# PCB-SSB-1x2b.net
KiCad netlist of a schematic drawn in EAGLE
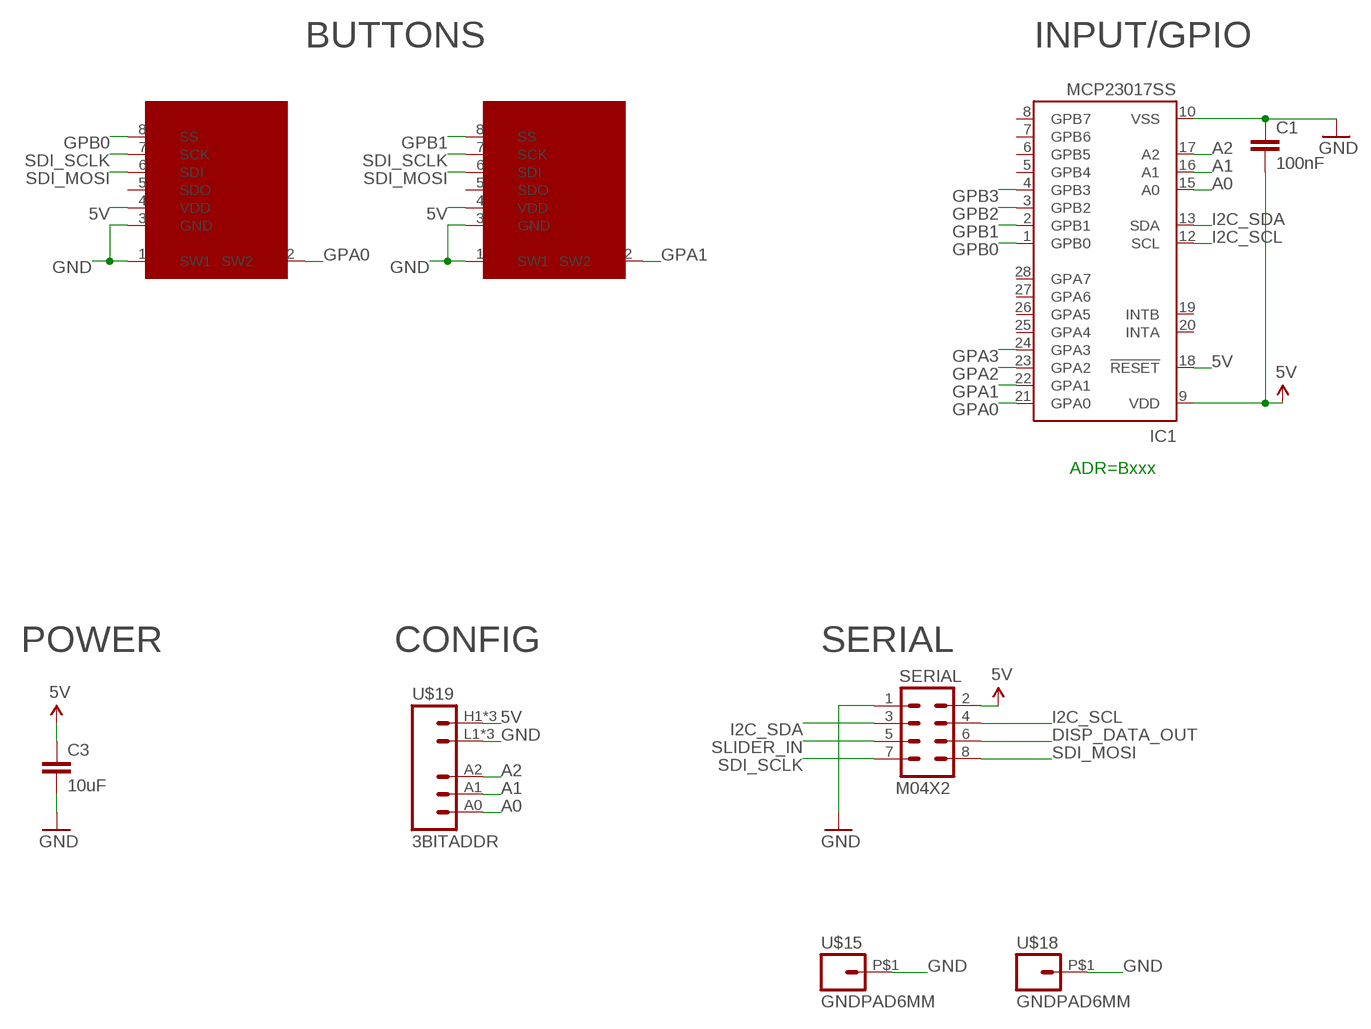
[diagram p0: schematic, sheet 1]

(export (version "E")
  (design (tool "Eeschema 10.0.6"))
  (components
    (comp (ref "C1")
      (value "100nF")
      (footprint "eagle-import:0603-CAP")
      (libsource (lib "eagle-import") (part "CAP0603-CAP"))
    )
    (comp (ref "C3")
      (value "10uF")
      (footprint "eagle-import:0805")
      (libsource (lib "eagle-import") (part "CAP0805"))
    )
    (comp (ref "IC1")
      (value "MCP23017SS")
      (footprint "eagle-import:SSOP28")
      (fields
        (field (name "MF") "MICROCHIP")
        (field (name "MPN") "MCP23017-E/SS")
        (field (name "MPN_1") "MCP23017-E/SS")
        (field (name "OC_FARNELL") "1467674")
        (field (name "OC_NEWARK") "31K2960")
      )
      (libsource (lib "eagle-import") (part "MCP23017SS"))
    )
    (comp (ref "SERIAL")
      (value "M04X2")
      (footprint "eagle-import:2X4")
      (libsource (lib "eagle-import") (part "M04X2"))
    )
    (comp (ref "SSW1")
      (value "SMART_SWITCHSMART_SWITCH_8PIN")
      (footprint "eagle-import:SMART_SWITCH")
      (libsource (lib "eagle-import") (part "SMART_SWITCHSMART_SWITCH_8PIN"))
    )
    (comp (ref "SSW2")
      (value "SMART_SWITCHSMART_SWITCH_8PIN")
      (footprint "eagle-import:SMART_SWITCH")
      (libsource (lib "eagle-import") (part "SMART_SWITCHSMART_SWITCH_8PIN"))
    )
    (comp (ref "U$15")
      (value "GNDPAD6MM")
      (footprint "eagle-import:3.2MMPAD6MM")
      (libsource (lib "eagle-import") (part "GNDPAD6MM"))
    )
    (comp (ref "U$18")
      (value "GNDPAD6MM")
      (footprint "eagle-import:3.2MMPAD6MM")
      (libsource (lib "eagle-import") (part "GNDPAD6MM"))
    )
    (comp (ref "U$19")
      (value "3BITADDR")
      (footprint "eagle-import:3BITADDR")
      (libsource (lib "eagle-import") (part "3BITADDR"))
    )
  )
  (nets
    (net (code "1") (name "/A0") (class "Default")
      (node (ref "IC1") (pin "15") (pinfunction "A0_15") (pintype "input"))
      (node (ref "U$19") (pin "A0") (pinfunction "A0_A0") (pintype "passive"))
    )
    (net (code "2") (name "/A1") (class "Default")
      (node (ref "IC1") (pin "16") (pinfunction "A1_16") (pintype "input"))
      (node (ref "U$19") (pin "A1") (pinfunction "A1_A1") (pintype "passive"))
    )
    (net (code "3") (name "/A2") (class "Default")
      (node (ref "IC1") (pin "17") (pinfunction "A2_17") (pintype "input"))
      (node (ref "U$19") (pin "A2") (pinfunction "A2_A2") (pintype "passive"))
    )
    (net (code "4") (name "/DISP_DATA_OUT") (class "Default")
      (node (ref "SERIAL") (pin "6") (pinfunction "6_6") (pintype "passive"))
    )
    (net (code "5") (name "/GPA0") (class "Default")
      (node (ref "IC1") (pin "21") (pinfunction "GPA0_21") (pintype "bidirectional"))
      (node (ref "SSW1") (pin "2") (pinfunction "SW2_2") (pintype "bidirectional"))
    )
    (net (code "6") (name "/GPA1") (class "Default")
      (node (ref "IC1") (pin "22") (pinfunction "GPA1_22") (pintype "bidirectional"))
      (node (ref "SSW2") (pin "2") (pinfunction "SW2_2") (pintype "bidirectional"))
    )
    (net (code "7") (name "/GPA2") (class "Default")
      (node (ref "IC1") (pin "23") (pinfunction "GPA2_23") (pintype "bidirectional"))
    )
    (net (code "8") (name "/GPA3") (class "Default")
      (node (ref "IC1") (pin "24") (pinfunction "GPA3_24") (pintype "bidirectional"))
    )
    (net (code "9") (name "/GPB0") (class "Default")
      (node (ref "IC1") (pin "1") (pinfunction "GPB0_1") (pintype "bidirectional"))
      (node (ref "SSW1") (pin "8") (pinfunction "SS_8") (pintype "bidirectional"))
    )
    (net (code "10") (name "/GPB1") (class "Default")
      (node (ref "IC1") (pin "2") (pinfunction "GPB1_2") (pintype "bidirectional"))
      (node (ref "SSW2") (pin "8") (pinfunction "SS_8") (pintype "bidirectional"))
    )
    (net (code "11") (name "/GPB2") (class "Default")
      (node (ref "IC1") (pin "3") (pinfunction "GPB2_3") (pintype "bidirectional"))
    )
    (net (code "12") (name "/GPB3") (class "Default")
      (node (ref "IC1") (pin "4") (pinfunction "GPB3_4") (pintype "bidirectional"))
    )
    (net (code "13") (name "/I2C_SCL") (class "Default")
      (node (ref "IC1") (pin "12") (pinfunction "SCL_12") (pintype "input"))
      (node (ref "SERIAL") (pin "4") (pinfunction "4_4") (pintype "passive"))
    )
    (net (code "14") (name "/I2C_SDA") (class "Default")
      (node (ref "IC1") (pin "13") (pinfunction "SDA_13") (pintype "bidirectional"))
      (node (ref "SERIAL") (pin "3") (pinfunction "3_3") (pintype "passive"))
    )
    (net (code "15") (name "/SDI_MOSI") (class "Default")
      (node (ref "SERIAL") (pin "8") (pinfunction "8_8") (pintype "passive"))
      (node (ref "SSW1") (pin "6") (pinfunction "SDI_6") (pintype "bidirectional"))
      (node (ref "SSW2") (pin "6") (pinfunction "SDI_6") (pintype "bidirectional"))
    )
    (net (code "16") (name "/SDI_SCLK") (class "Default")
      (node (ref "SERIAL") (pin "7") (pinfunction "7_7") (pintype "passive"))
      (node (ref "SSW1") (pin "7") (pinfunction "SCK_7") (pintype "bidirectional"))
      (node (ref "SSW2") (pin "7") (pinfunction "SCK_7") (pintype "bidirectional"))
    )
    (net (code "17") (name "/SLIDER_IN") (class "Default")
      (node (ref "SERIAL") (pin "5") (pinfunction "5_5") (pintype "passive"))
    )
    (net (code "18") (name "5V") (class "Default")
      (node (ref "C1") (pin "2") (pinfunction "2_2") (pintype "passive"))
      (node (ref "C3") (pin "1") (pinfunction "1_1") (pintype "passive"))
      (node (ref "IC1") (pin "18") (pinfunction "~{RESET}_18") (pintype "input"))
      (node (ref "IC1") (pin "9") (pinfunction "VDD_9") (pintype "power_in"))
      (node (ref "SERIAL") (pin "2") (pinfunction "2_2") (pintype "passive"))
      (node (ref "SSW1") (pin "4") (pinfunction "VDD_4") (pintype "bidirectional"))
      (node (ref "SSW2") (pin "4") (pinfunction "VDD_4") (pintype "bidirectional"))
      (node (ref "U$19") (pin "H1") (pinfunction "VCC_H1") (pintype "passive"))
      (node (ref "U$19") (pin "H2") (pinfunction "VCC_H2") (pintype "passive"))
      (node (ref "U$19") (pin "H3") (pinfunction "VCC_H3") (pintype "passive"))
    )
    (net (code "19") (name "GND") (class "Default")
      (node (ref "C1") (pin "1") (pinfunction "1_1") (pintype "passive"))
      (node (ref "C3") (pin "2") (pinfunction "2_2") (pintype "passive"))
      (node (ref "IC1") (pin "10") (pinfunction "VSS_10") (pintype "power_in"))
      (node (ref "SERIAL") (pin "1") (pinfunction "1_1") (pintype "passive"))
      (node (ref "SSW1") (pin "1") (pinfunction "SW1_1") (pintype "bidirectional"))
      (node (ref "SSW1") (pin "3") (pinfunction "GND_3") (pintype "bidirectional"))
      (node (ref "SSW2") (pin "1") (pinfunction "SW1_1") (pintype "bidirectional"))
      (node (ref "SSW2") (pin "3") (pinfunction "GND_3") (pintype "bidirectional"))
      (node (ref "U$15") (pin "P$1") (pinfunction "1_P$1") (pintype "passive"))
      (node (ref "U$18") (pin "P$1") (pinfunction "1_P$1") (pintype "passive"))
      (node (ref "U$19") (pin "L1") (pinfunction "GND_L1") (pintype "passive"))
      (node (ref "U$19") (pin "L2") (pinfunction "GND_L2") (pintype "passive"))
      (node (ref "U$19") (pin "L3") (pinfunction "GND_L3") (pintype "passive"))
    )
    (net (code "20") (name "unconnected-(IC1-GPA4-Pad25)") (class "Default")
      (node (ref "IC1") (pin "25") (pinfunction "GPA4_25") (pintype "bidirectional"))
    )
    (net (code "21") (name "unconnected-(IC1-GPA5-Pad26)") (class "Default")
      (node (ref "IC1") (pin "26") (pinfunction "GPA5_26") (pintype "bidirectional"))
    )
    (net (code "22") (name "unconnected-(IC1-GPA6-Pad27)") (class "Default")
      (node (ref "IC1") (pin "27") (pinfunction "GPA6_27") (pintype "bidirectional"))
    )
    (net (code "23") (name "unconnected-(IC1-GPA7-Pad28)") (class "Default")
      (node (ref "IC1") (pin "28") (pinfunction "GPA7_28") (pintype "bidirectional"))
    )
    (net (code "24") (name "unconnected-(IC1-GPB4-Pad5)") (class "Default")
      (node (ref "IC1") (pin "5") (pinfunction "GPB4_5") (pintype "bidirectional"))
    )
    (net (code "25") (name "unconnected-(IC1-GPB5-Pad6)") (class "Default")
      (node (ref "IC1") (pin "6") (pinfunction "GPB5_6") (pintype "bidirectional"))
    )
    (net (code "26") (name "unconnected-(IC1-GPB6-Pad7)") (class "Default")
      (node (ref "IC1") (pin "7") (pinfunction "GPB6_7") (pintype "bidirectional"))
    )
    (net (code "27") (name "unconnected-(IC1-GPB7-Pad8)") (class "Default")
      (node (ref "IC1") (pin "8") (pinfunction "GPB7_8") (pintype "bidirectional"))
    )
    (net (code "28") (name "unconnected-(IC1-INTA-Pad20)") (class "Default")
      (node (ref "IC1") (pin "20") (pinfunction "INTA_20") (pintype "output"))
    )
    (net (code "29") (name "unconnected-(IC1-INTB-Pad19)") (class "Default")
      (node (ref "IC1") (pin "19") (pinfunction "INTB_19") (pintype "output"))
    )
    (net (code "30") (name "unconnected-(SSW1-SDO-Pad5)") (class "Default")
      (node (ref "SSW1") (pin "5") (pinfunction "SDO_5") (pintype "bidirectional"))
    )
    (net (code "31") (name "unconnected-(SSW2-SDO-Pad5)") (class "Default")
      (node (ref "SSW2") (pin "5") (pinfunction "SDO_5") (pintype "bidirectional"))
    )
  )
)
